# AD_breakout.net
KiCad netlist of a schematic drawn in EAGLE
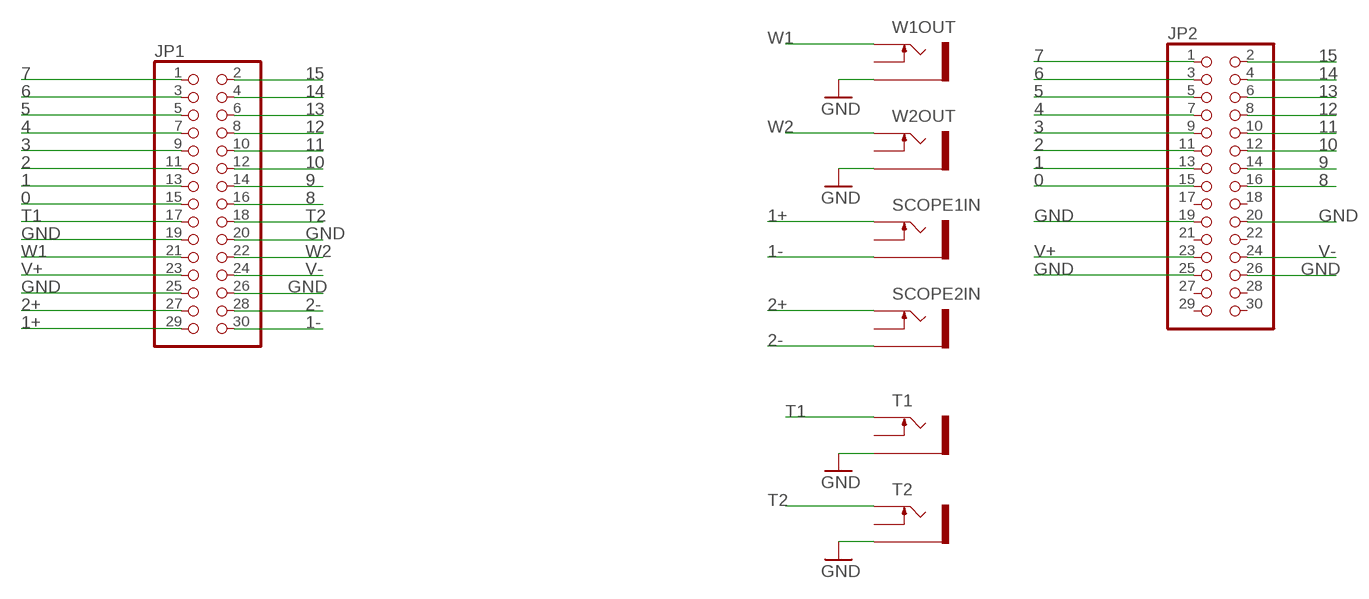
[diagram p0: schematic, sheet 1]

(export (version "E")
  (design (tool "Eeschema 10.0.6"))
  (components
    (comp (ref "JP1")
      (value "PINHD-2X15")
      (footprint "eagle-import:2X15")
      (libsource (lib "eagle-import") (part "PINHD-2X15"))
    )
    (comp (ref "JP2")
      (value "PINHD-2X15")
      (footprint "eagle-import:2X15")
      (libsource (lib "eagle-import") (part "PINHD-2X15"))
    )
    (comp (ref "SCOPE1IN")
      (value "THONKICONNNEW")
      (footprint "eagle-import:WQP-PJ301M-12_JACK")
      (libsource (lib "eagle-import") (part "THONKICONNNEW"))
    )
    (comp (ref "SCOPE2IN")
      (value "THONKICONNNEW")
      (footprint "eagle-import:WQP-PJ301M-12_JACK")
      (libsource (lib "eagle-import") (part "THONKICONNNEW"))
    )
    (comp (ref "T1")
      (value "THONKICONNNEW")
      (footprint "eagle-import:WQP-PJ301M-12_JACK")
      (libsource (lib "eagle-import") (part "THONKICONNNEW"))
    )
    (comp (ref "T2")
      (value "THONKICONNNEW")
      (footprint "eagle-import:WQP-PJ301M-12_JACK")
      (libsource (lib "eagle-import") (part "THONKICONNNEW"))
    )
    (comp (ref "W1OUT")
      (value "THONKICONNNEW")
      (footprint "eagle-import:WQP-PJ301M-12_JACK")
      (libsource (lib "eagle-import") (part "THONKICONNNEW"))
    )
    (comp (ref "W2OUT")
      (value "THONKICONNNEW")
      (footprint "eagle-import:WQP-PJ301M-12_JACK")
      (libsource (lib "eagle-import") (part "THONKICONNNEW"))
    )
  )
  (nets
    (net (code "1") (name "/0") (class "Default")
      (node (ref "JP1") (pin "15") (pinfunction "15_15") (pintype "passive"))
      (node (ref "JP2") (pin "15") (pinfunction "15_15") (pintype "passive"))
    )
    (net (code "2") (name "/1") (class "Default")
      (node (ref "JP1") (pin "13") (pinfunction "13_13") (pintype "passive"))
      (node (ref "JP2") (pin "13") (pinfunction "13_13") (pintype "passive"))
    )
    (net (code "3") (name "/1+") (class "Default")
      (node (ref "JP1") (pin "29") (pinfunction "29_29") (pintype "passive"))
      (node (ref "SCOPE1IN") (pin "P$1_TIP") (pinfunction "TIP_P$1_TIP") (pintype "passive"))
    )
    (net (code "4") (name "/1-") (class "Default")
      (node (ref "JP1") (pin "30") (pinfunction "30_30") (pintype "passive"))
      (node (ref "SCOPE1IN") (pin "P$3_SLEEVE") (pinfunction "SLEEVE_P$3_SLEEVE") (pintype "passive"))
    )
    (net (code "5") (name "/2") (class "Default")
      (node (ref "JP1") (pin "11") (pinfunction "11_11") (pintype "passive"))
      (node (ref "JP2") (pin "11") (pinfunction "11_11") (pintype "passive"))
    )
    (net (code "6") (name "/2+") (class "Default")
      (node (ref "JP1") (pin "27") (pinfunction "27_27") (pintype "passive"))
      (node (ref "SCOPE2IN") (pin "P$1_TIP") (pinfunction "TIP_P$1_TIP") (pintype "passive"))
    )
    (net (code "7") (name "/2-") (class "Default")
      (node (ref "JP1") (pin "28") (pinfunction "28_28") (pintype "passive"))
      (node (ref "SCOPE2IN") (pin "P$3_SLEEVE") (pinfunction "SLEEVE_P$3_SLEEVE") (pintype "passive"))
    )
    (net (code "8") (name "/3") (class "Default")
      (node (ref "JP1") (pin "9") (pinfunction "9_9") (pintype "passive"))
      (node (ref "JP2") (pin "9") (pinfunction "9_9") (pintype "passive"))
    )
    (net (code "9") (name "/4") (class "Default")
      (node (ref "JP1") (pin "7") (pinfunction "7_7") (pintype "passive"))
      (node (ref "JP2") (pin "7") (pinfunction "7_7") (pintype "passive"))
    )
    (net (code "10") (name "/5") (class "Default")
      (node (ref "JP1") (pin "5") (pinfunction "5_5") (pintype "passive"))
      (node (ref "JP2") (pin "5") (pinfunction "5_5") (pintype "passive"))
    )
    (net (code "11") (name "/6") (class "Default")
      (node (ref "JP1") (pin "3") (pinfunction "3_3") (pintype "passive"))
      (node (ref "JP2") (pin "3") (pinfunction "3_3") (pintype "passive"))
    )
    (net (code "12") (name "/7") (class "Default")
      (node (ref "JP1") (pin "1") (pinfunction "1_1") (pintype "passive"))
      (node (ref "JP2") (pin "1") (pinfunction "1_1") (pintype "passive"))
    )
    (net (code "13") (name "/8") (class "Default")
      (node (ref "JP1") (pin "16") (pinfunction "16_16") (pintype "passive"))
      (node (ref "JP2") (pin "16") (pinfunction "16_16") (pintype "passive"))
    )
    (net (code "14") (name "/9") (class "Default")
      (node (ref "JP1") (pin "14") (pinfunction "14_14") (pintype "passive"))
      (node (ref "JP2") (pin "14") (pinfunction "14_14") (pintype "passive"))
    )
    (net (code "15") (name "/10") (class "Default")
      (node (ref "JP1") (pin "12") (pinfunction "12_12") (pintype "passive"))
      (node (ref "JP2") (pin "12") (pinfunction "12_12") (pintype "passive"))
    )
    (net (code "16") (name "/11") (class "Default")
      (node (ref "JP1") (pin "10") (pinfunction "10_10") (pintype "passive"))
      (node (ref "JP2") (pin "10") (pinfunction "10_10") (pintype "passive"))
    )
    (net (code "17") (name "/12") (class "Default")
      (node (ref "JP1") (pin "8") (pinfunction "8_8") (pintype "passive"))
      (node (ref "JP2") (pin "8") (pinfunction "8_8") (pintype "passive"))
    )
    (net (code "18") (name "/13") (class "Default")
      (node (ref "JP1") (pin "6") (pinfunction "6_6") (pintype "passive"))
      (node (ref "JP2") (pin "6") (pinfunction "6_6") (pintype "passive"))
    )
    (net (code "19") (name "/14") (class "Default")
      (node (ref "JP1") (pin "4") (pinfunction "4_4") (pintype "passive"))
      (node (ref "JP2") (pin "4") (pinfunction "4_4") (pintype "passive"))
    )
    (net (code "20") (name "/15") (class "Default")
      (node (ref "JP1") (pin "2") (pinfunction "2_2") (pintype "passive"))
      (node (ref "JP2") (pin "2") (pinfunction "2_2") (pintype "passive"))
    )
    (net (code "21") (name "/T1") (class "Default")
      (node (ref "JP1") (pin "17") (pinfunction "17_17") (pintype "passive"))
      (node (ref "T1") (pin "P$1_TIP") (pinfunction "TIP_P$1_TIP") (pintype "passive"))
    )
    (net (code "22") (name "/T2") (class "Default")
      (node (ref "JP1") (pin "18") (pinfunction "18_18") (pintype "passive"))
      (node (ref "T2") (pin "P$1_TIP") (pinfunction "TIP_P$1_TIP") (pintype "passive"))
    )
    (net (code "23") (name "/V+") (class "Default")
      (node (ref "JP1") (pin "23") (pinfunction "23_23") (pintype "passive"))
      (node (ref "JP2") (pin "23") (pinfunction "23_23") (pintype "passive"))
    )
    (net (code "24") (name "/V-") (class "Default")
      (node (ref "JP1") (pin "24") (pinfunction "24_24") (pintype "passive"))
      (node (ref "JP2") (pin "24") (pinfunction "24_24") (pintype "passive"))
    )
    (net (code "25") (name "/W1") (class "Default")
      (node (ref "JP1") (pin "21") (pinfunction "21_21") (pintype "passive"))
      (node (ref "W1OUT") (pin "P$1_TIP") (pinfunction "TIP_P$1_TIP") (pintype "passive"))
    )
    (net (code "26") (name "/W2") (class "Default")
      (node (ref "JP1") (pin "22") (pinfunction "22_22") (pintype "passive"))
      (node (ref "W2OUT") (pin "P$1_TIP") (pinfunction "TIP_P$1_TIP") (pintype "passive"))
    )
    (net (code "27") (name "GND") (class "Default")
      (node (ref "JP1") (pin "19") (pinfunction "19_19") (pintype "passive"))
      (node (ref "JP1") (pin "20") (pinfunction "20_20") (pintype "passive"))
      (node (ref "JP1") (pin "25") (pinfunction "25_25") (pintype "passive"))
      (node (ref "JP1") (pin "26") (pinfunction "26_26") (pintype "passive"))
      (node (ref "JP2") (pin "19") (pinfunction "19_19") (pintype "passive"))
      (node (ref "JP2") (pin "20") (pinfunction "20_20") (pintype "passive"))
      (node (ref "JP2") (pin "25") (pinfunction "25_25") (pintype "passive"))
      (node (ref "JP2") (pin "26") (pinfunction "26_26") (pintype "passive"))
      (node (ref "T1") (pin "P$3_SLEEVE") (pinfunction "SLEEVE_P$3_SLEEVE") (pintype "passive"))
      (node (ref "T2") (pin "P$3_SLEEVE") (pinfunction "SLEEVE_P$3_SLEEVE") (pintype "passive"))
      (node (ref "W1OUT") (pin "P$3_SLEEVE") (pinfunction "SLEEVE_P$3_SLEEVE") (pintype "passive"))
      (node (ref "W2OUT") (pin "P$3_SLEEVE") (pinfunction "SLEEVE_P$3_SLEEVE") (pintype "passive"))
    )
    (net (code "28") (name "unconnected-(JP2-Pad17)") (class "Default")
      (node (ref "JP2") (pin "17") (pinfunction "17_17") (pintype "passive"))
    )
    (net (code "29") (name "unconnected-(JP2-Pad18)") (class "Default")
      (node (ref "JP2") (pin "18") (pinfunction "18_18") (pintype "passive"))
    )
    (net (code "30") (name "unconnected-(JP2-Pad21)") (class "Default")
      (node (ref "JP2") (pin "21") (pinfunction "21_21") (pintype "passive"))
    )
    (net (code "31") (name "unconnected-(JP2-Pad22)") (class "Default")
      (node (ref "JP2") (pin "22") (pinfunction "22_22") (pintype "passive"))
    )
    (net (code "32") (name "unconnected-(JP2-Pad27)") (class "Default")
      (node (ref "JP2") (pin "27") (pinfunction "27_27") (pintype "passive"))
    )
    (net (code "33") (name "unconnected-(JP2-Pad28)") (class "Default")
      (node (ref "JP2") (pin "28") (pinfunction "28_28") (pintype "passive"))
    )
    (net (code "34") (name "unconnected-(JP2-Pad29)") (class "Default")
      (node (ref "JP2") (pin "29") (pinfunction "29_29") (pintype "passive"))
    )
    (net (code "35") (name "unconnected-(JP2-Pad30)") (class "Default")
      (node (ref "JP2") (pin "30") (pinfunction "30_30") (pintype "passive"))
    )
    (net (code "36") (name "unconnected-(SCOPE1IN-SWITCH-PadP$2_SWITCH)") (class "Default")
      (node (ref "SCOPE1IN") (pin "P$2_SWITCH") (pinfunction "SWITCH_P$2_SWITCH") (pintype "passive"))
    )
    (net (code "37") (name "unconnected-(SCOPE2IN-SWITCH-PadP$2_SWITCH)") (class "Default")
      (node (ref "SCOPE2IN") (pin "P$2_SWITCH") (pinfunction "SWITCH_P$2_SWITCH") (pintype "passive"))
    )
    (net (code "38") (name "unconnected-(T1-SWITCH-PadP$2_SWITCH)") (class "Default")
      (node (ref "T1") (pin "P$2_SWITCH") (pinfunction "SWITCH_P$2_SWITCH") (pintype "passive"))
    )
    (net (code "39") (name "unconnected-(T2-SWITCH-PadP$2_SWITCH)") (class "Default")
      (node (ref "T2") (pin "P$2_SWITCH") (pinfunction "SWITCH_P$2_SWITCH") (pintype "passive"))
    )
    (net (code "40") (name "unconnected-(W1OUT-SWITCH-PadP$2_SWITCH)") (class "Default")
      (node (ref "W1OUT") (pin "P$2_SWITCH") (pinfunction "SWITCH_P$2_SWITCH") (pintype "passive"))
    )
    (net (code "41") (name "unconnected-(W2OUT-SWITCH-PadP$2_SWITCH)") (class "Default")
      (node (ref "W2OUT") (pin "P$2_SWITCH") (pinfunction "SWITCH_P$2_SWITCH") (pintype "passive"))
    )
  )
)
